# Servo-Steuer-Schaltung.net
KiCad netlist of a schematic drawn in EAGLE
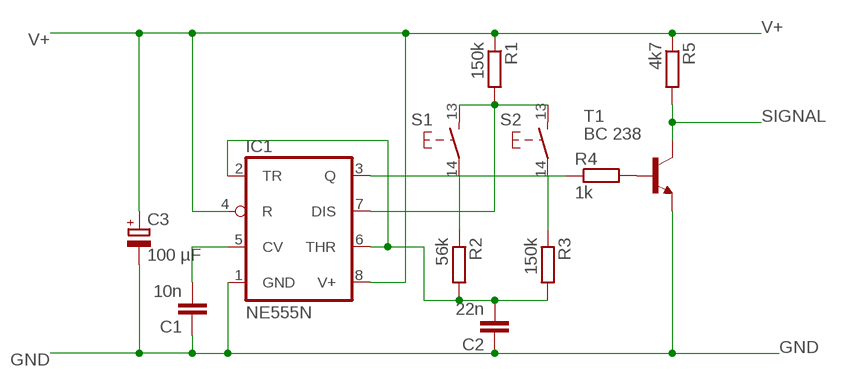
[diagram p0: schematic, sheet 1]

(export (version "E")
  (design (tool "Eeschema 10.0.6"))
  (components
    (comp (ref "C1")
      (value "10n")
      (footprint "eagle-import:C10B4")
      (libsource (lib "eagle-import") (part "C10/4"))
    )
    (comp (ref "C2")
      (value "22n")
      (footprint "eagle-import:C10B4")
      (libsource (lib "eagle-import") (part "C10/4"))
    )
    (comp (ref "C3")
      (value "100 µF")
      (footprint "eagle-import:E2,5-7")
      (libsource (lib "eagle-import") (part "CPOL-EUE2.5-7"))
    )
    (comp (ref "IC1")
      (value "NE555N")
      (footprint "eagle-import:DIL08")
      (libsource (lib "eagle-import") (part "555NNE"))
    )
    (comp (ref "R1")
      (value "150k")
      (footprint "eagle-import:0207_10")
      (libsource (lib "eagle-import") (part "R-EU_0207/10"))
    )
    (comp (ref "R2")
      (value "56k")
      (footprint "eagle-import:0207_10")
      (libsource (lib "eagle-import") (part "R-EU_0207/10"))
    )
    (comp (ref "R3")
      (value "150k")
      (footprint "eagle-import:0207_10")
      (libsource (lib "eagle-import") (part "R-EU_0207/10"))
    )
    (comp (ref "R4")
      (value "1k")
      (footprint "eagle-import:0207_10")
      (libsource (lib "eagle-import") (part "R-EU_0207/10"))
    )
    (comp (ref "R5")
      (value "4k7")
      (footprint "eagle-import:0207_10")
      (libsource (lib "eagle-import") (part "R-EU_0207/10"))
    )
    (comp (ref "S1")
      (value "TASTER_SCHLIESSER")
      (footprint "eagle-import:EINTASTER")
      (libsource (lib "eagle-import") (part "TASTER_SCHLIESSER"))
    )
    (comp (ref "S2")
      (value "TASTER_SCHLIESSER")
      (footprint "eagle-import:EINTASTER")
      (libsource (lib "eagle-import") (part "TASTER_SCHLIESSER"))
    )
    (comp (ref "T1")
      (value "BC 238")
      (footprint "eagle-import:TO92-CBE")
      (libsource (lib "eagle-import") (part "-NPN-TO92-CBEBC547A"))
    )
  )
  (nets
    (net (code "1") (name "/GND") (class "Default")
      (node (ref "C1") (pin "1") (pinfunction "1_1") (pintype "passive"))
      (node (ref "C2") (pin "1") (pinfunction "1_1") (pintype "passive"))
      (node (ref "C3") (pin "-") (pinfunction "-_-") (pintype "passive"))
      (node (ref "IC1") (pin "1") (pinfunction "GND_1") (pintype "power_in"))
      (node (ref "T1") (pin "E") (pinfunction "E_E") (pintype "passive"))
    )
    (net (code "2") (name "/SIGNAL") (class "Default")
      (node (ref "R5") (pin "2") (pinfunction "2_2") (pintype "passive"))
      (node (ref "T1") (pin "C") (pinfunction "C_C") (pintype "passive"))
    )
    (net (code "3") (name "/V+") (class "Default")
      (node (ref "C3") (pin "+") (pinfunction "+_+") (pintype "passive"))
      (node (ref "IC1") (pin "4") (pinfunction "R_4") (pintype "input"))
      (node (ref "IC1") (pin "8") (pinfunction "V+_8") (pintype "power_in"))
      (node (ref "R1") (pin "1") (pinfunction "1_1") (pintype "passive"))
      (node (ref "R5") (pin "1") (pinfunction "1_1") (pintype "passive"))
    )
    (net (code "4") (name "Net-(IC1-CV)") (class "Default")
      (node (ref "C1") (pin "2") (pinfunction "2_2") (pintype "passive"))
      (node (ref "IC1") (pin "5") (pinfunction "CV_5") (pintype "input"))
    )
    (net (code "5") (name "Net-(IC1-DIS)") (class "Default")
      (node (ref "IC1") (pin "7") (pinfunction "DIS_7") (pintype "input"))
      (node (ref "R1") (pin "2") (pinfunction "2_2") (pintype "passive"))
      (node (ref "S1") (pin "13") (pinfunction "13_13") (pintype "passive"))
      (node (ref "S2") (pin "13") (pinfunction "13_13") (pintype "passive"))
    )
    (net (code "6") (name "Net-(IC1-Q)") (class "Default")
      (node (ref "IC1") (pin "3") (pinfunction "Q_3") (pintype "output"))
      (node (ref "R4") (pin "1") (pinfunction "1_1") (pintype "passive"))
    )
    (net (code "7") (name "Net-(IC1-THR)") (class "Default")
      (node (ref "C2") (pin "2") (pinfunction "2_2") (pintype "passive"))
      (node (ref "IC1") (pin "2") (pinfunction "TR_2") (pintype "input"))
      (node (ref "IC1") (pin "6") (pinfunction "THR_6") (pintype "input"))
      (node (ref "R2") (pin "2") (pinfunction "2_2") (pintype "passive"))
      (node (ref "R3") (pin "2") (pinfunction "2_2") (pintype "passive"))
    )
    (net (code "8") (name "Net-(R2-Pad1)") (class "Default")
      (node (ref "R2") (pin "1") (pinfunction "1_1") (pintype "passive"))
      (node (ref "S1") (pin "14") (pinfunction "14_14") (pintype "passive"))
    )
    (net (code "9") (name "Net-(R3-Pad1)") (class "Default")
      (node (ref "R3") (pin "1") (pinfunction "1_1") (pintype "passive"))
      (node (ref "S2") (pin "14") (pinfunction "14_14") (pintype "passive"))
    )
    (net (code "10") (name "Net-(R4-Pad2)") (class "Default")
      (node (ref "R4") (pin "2") (pinfunction "2_2") (pintype "passive"))
      (node (ref "T1") (pin "B") (pinfunction "B_B") (pintype "passive"))
    )
  )
)
